# 220VAC_power_control.net
KiCad netlist of a schematic drawn in EAGLE
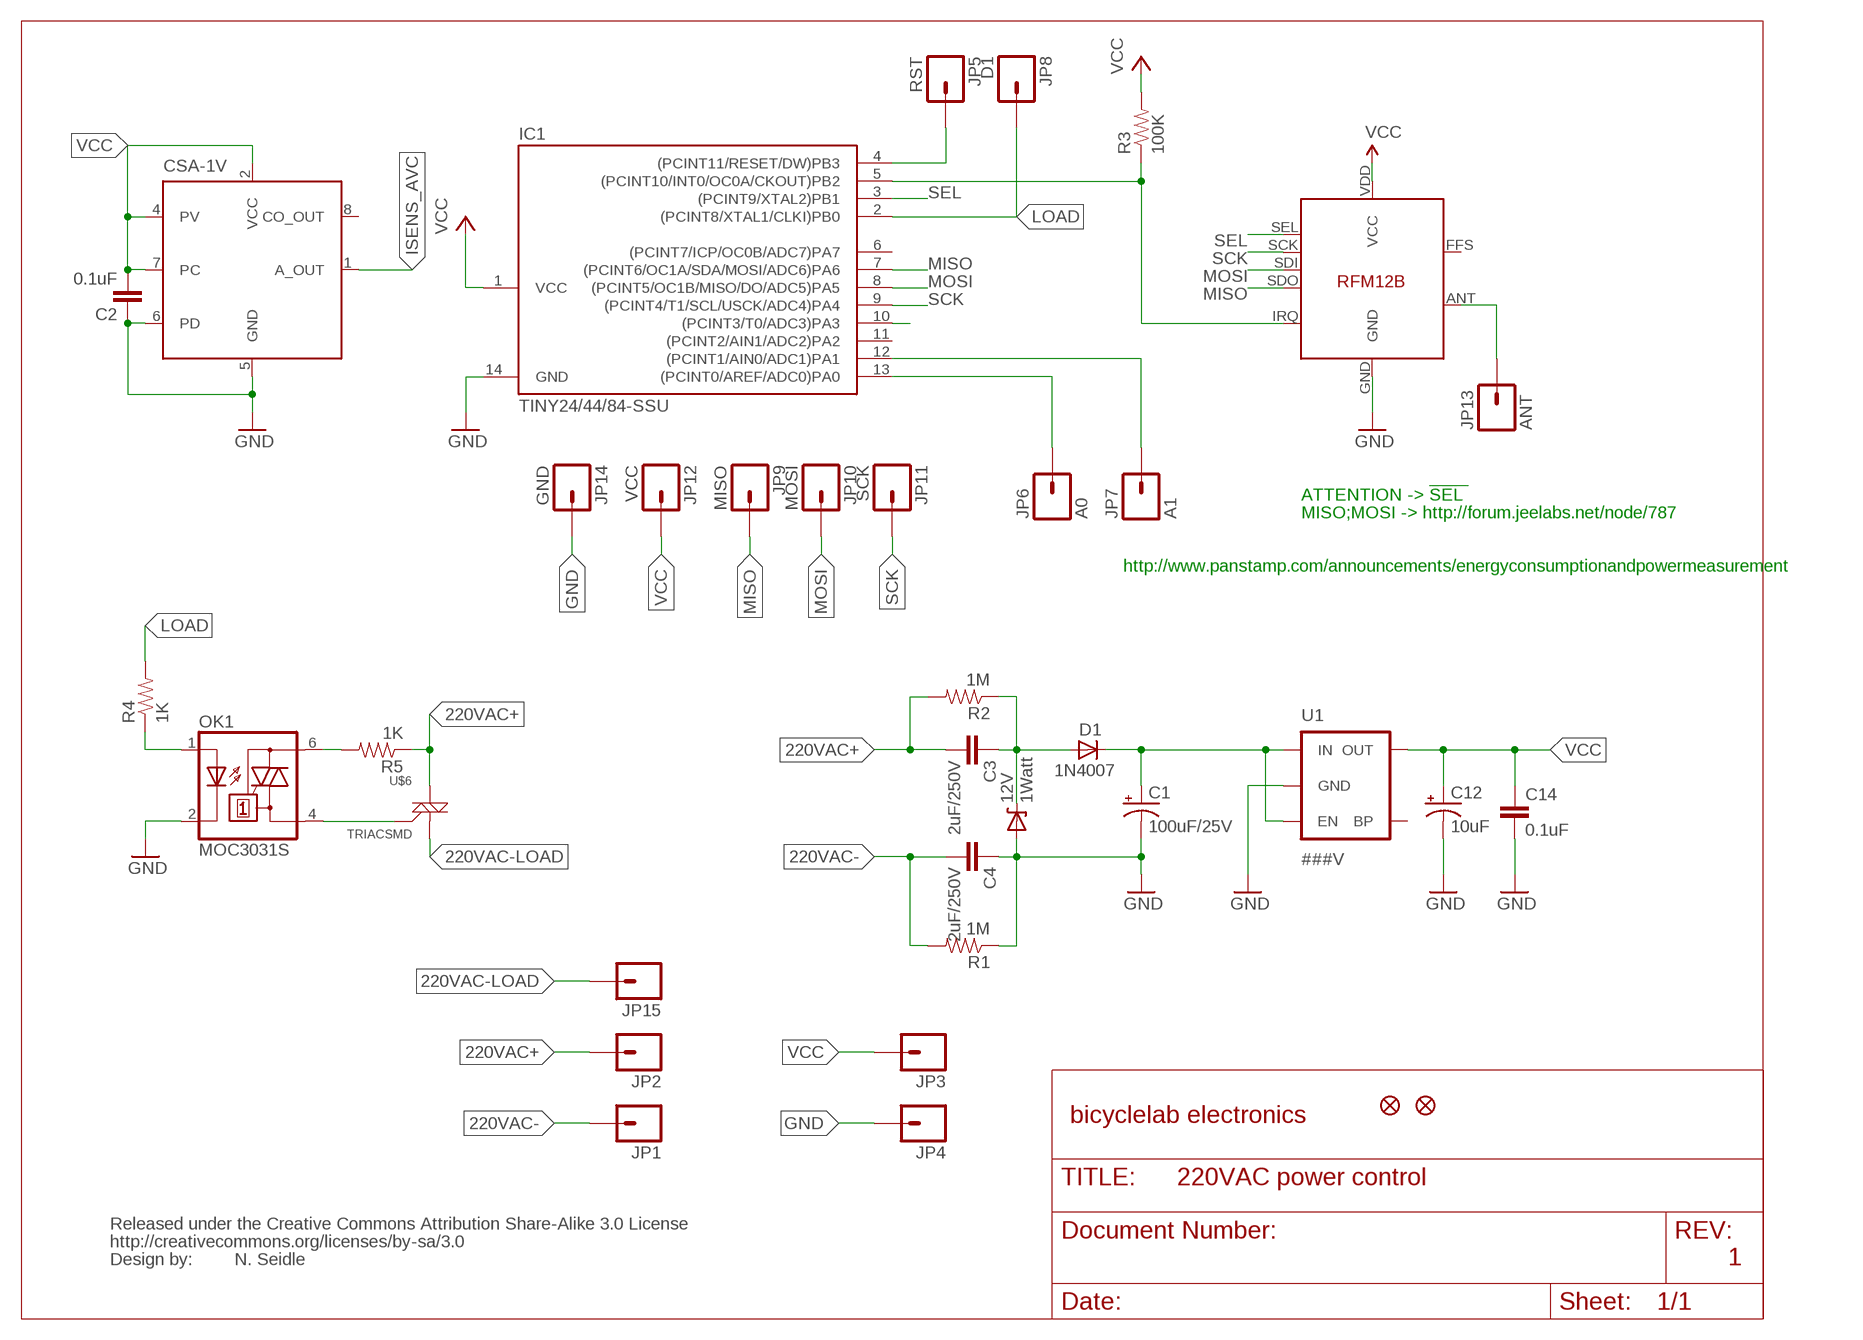
[diagram p0: schematic, sheet 1]

(export (version "E")
  (design (tool "Eeschema 10.0.6"))
  (components
    (comp (ref "12V")
      (value "1Watt")
      (footprint "eagle-import:SMB-DIODE")
      (libsource (lib "eagle-import") (part "DIODE-ZENERSMB"))
    )
    (comp (ref "C1")
      (value "100uF/25V")
      (footprint "eagle-import:EIA7343")
      (libsource (lib "eagle-import") (part "CAP_POL7343"))
    )
    (comp (ref "C2")
      (value "0.1uF")
      (footprint "eagle-import:0603-CAP")
      (libsource (lib "eagle-import") (part "CAP0603-CAP"))
    )
    (comp (ref "C3")
      (value "2uF/250V")
      (footprint "eagle-import:0402-CAP")
      (libsource (lib "eagle-import") (part "CAP0402-CAP"))
    )
    (comp (ref "C4")
      (value "2uF/250V")
      (footprint "eagle-import:0402-CAP")
      (libsource (lib "eagle-import") (part "CAP0402-CAP"))
    )
    (comp (ref "C12")
      (value "10uF")
      (footprint "eagle-import:EIA3216")
      (libsource (lib "eagle-import") (part "CAP_POL1206"))
    )
    (comp (ref "C14")
      (value "0.1uF")
      (footprint "eagle-import:0603-CAP")
      (libsource (lib "eagle-import") (part "CAP0603-CAP"))
    )
    (comp (ref "D1")
      (value "1N4007")
      (footprint "eagle-import:SMA-DIODE")
      (libsource (lib "eagle-import") (part "DIODESMA"))
    )
    (comp (ref "IC1")
      (value "TINY24/44/84-SSU")
      (footprint "eagle-import:SOIC14")
      (libsource (lib "eagle-import") (part "TINY24/44/84-SSU"))
    )
    (comp (ref "JP1")
      (value "M01PTH")
      (footprint "eagle-import:1X01")
      (libsource (lib "eagle-import") (part "M01PTH"))
    )
    (comp (ref "JP2")
      (value "M01PTH")
      (footprint "eagle-import:1X01")
      (libsource (lib "eagle-import") (part "M01PTH"))
    )
    (comp (ref "JP3")
      (value "M01PTH")
      (footprint "eagle-import:1X01")
      (libsource (lib "eagle-import") (part "M01PTH"))
    )
    (comp (ref "JP4")
      (value "M01PTH")
      (footprint "eagle-import:1X01")
      (libsource (lib "eagle-import") (part "M01PTH"))
    )
    (comp (ref "JP5")
      (value "RST")
      (footprint "eagle-import:1X01_POGOPIN_HOLE_0.58")
      (libsource (lib "eagle-import") (part "M01POGOPIN_HOLE_0.58"))
    )
    (comp (ref "JP6")
      (value "A0")
      (footprint "eagle-import:1X01_POGOPIN_HOLE_0.58")
      (libsource (lib "eagle-import") (part "M01POGOPIN_HOLE_0.58"))
    )
    (comp (ref "JP7")
      (value "A1")
      (footprint "eagle-import:1X01_POGOPIN_HOLE_0.58")
      (libsource (lib "eagle-import") (part "M01POGOPIN_HOLE_0.58"))
    )
    (comp (ref "JP8")
      (value "D1")
      (footprint "eagle-import:1X01_POGOPIN_HOLE_0.58")
      (libsource (lib "eagle-import") (part "M01POGOPIN_HOLE_0.58"))
    )
    (comp (ref "JP9")
      (value "MISO")
      (footprint "eagle-import:1X01_POGOPIN_HOLE_0.58")
      (libsource (lib "eagle-import") (part "M01POGOPIN_HOLE_0.58"))
    )
    (comp (ref "JP10")
      (value "MOSI")
      (footprint "eagle-import:1X01_POGOPIN_HOLE_0.58")
      (libsource (lib "eagle-import") (part "M01POGOPIN_HOLE_0.58"))
    )
    (comp (ref "JP11")
      (value "SCK")
      (footprint "eagle-import:1X01_POGOPIN_HOLE_0.58")
      (libsource (lib "eagle-import") (part "M01POGOPIN_HOLE_0.58"))
    )
    (comp (ref "JP12")
      (value "VCC")
      (footprint "eagle-import:1X01_POGOPIN_HOLE_0.58")
      (libsource (lib "eagle-import") (part "M01POGOPIN_HOLE_0.58"))
    )
    (comp (ref "JP13")
      (value "ANT")
      (footprint "eagle-import:PAD-1.5X4.5")
      (libsource (lib "eagle-import") (part "M01SMD-4.5X1.5"))
    )
    (comp (ref "JP14")
      (value "GND")
      (footprint "eagle-import:1X01NS")
      (libsource (lib "eagle-import") (part "M01SMDNS"))
    )
    (comp (ref "JP15")
      (value "M01PTH")
      (footprint "eagle-import:1X01")
      (libsource (lib "eagle-import") (part "M01PTH"))
    )
    (comp (ref "OK1")
      (value "MOC3031S")
      (footprint "eagle-import:DIL6-SMD")
      (fields (field (name "MF") "FAIRCHILD SEMICONDUCTOR") (field (name "MPN") "MOC3031SM"))
      (libsource (lib "eagle-import") (part "MOC30S31"))
    )
    (comp (ref "R1")
      (value "1M")
      (footprint "eagle-import:0402-RES")
      (libsource (lib "eagle-import") (part "RESISTOR0402-RES"))
    )
    (comp (ref "R2")
      (value "1M")
      (footprint "eagle-import:0402-RES")
      (libsource (lib "eagle-import") (part "RESISTOR0402-RES"))
    )
    (comp (ref "R3")
      (value "100K")
      (footprint "eagle-import:0805")
      (libsource (lib "eagle-import") (part "RESISTOR0805-RES"))
    )
    (comp (ref "R4")
      (value "1K")
      (footprint "eagle-import:0805")
      (libsource (lib "eagle-import") (part "RESISTOR0805-RES"))
    )
    (comp (ref "R5")
      (value "1K")
      (footprint "eagle-import:0805")
      (libsource (lib "eagle-import") (part "RESISTOR0805-RES"))
    )
    (comp (ref "U$1")
      (value "CSA-1V")
      (footprint "eagle-import:SOIC8")
      (libsource (lib "eagle-import") (part "CSA-1V"))
    )
    (comp (ref "U$2")
      (value "RFM12B")
      (footprint "eagle-import:RFM12B")
      (libsource (lib "eagle-import") (part "RFM12B"))
    )
    (comp (ref "U$3")
      (value "FIDUCIAL1X2")
      (footprint "eagle-import:FIDUCIAL-1X2")
      (libsource (lib "eagle-import") (part "FIDUCIAL1X2"))
    )
    (comp (ref "U$4")
      (value "FIDUCIAL1X2")
      (footprint "eagle-import:FIDUCIAL-1X2")
      (libsource (lib "eagle-import") (part "FIDUCIAL1X2"))
    )
    (comp (ref "U$5")
      (value "CREATIVE_COMMONS")
      (footprint "eagle-import:CREATIVE_COMMONS")
      (libsource (lib "eagle-import") (part "CREATIVE_COMMONS"))
    )
    (comp (ref "U$6")
      (value "TRIACSMD")
      (footprint "eagle-import:SOT223")
      (libsource (lib "eagle-import") (part "TRIACSMD"))
    )
    (comp (ref "U1")
      (value "###V")
      (footprint "eagle-import:SOT23-5")
      (libsource (lib "eagle-import") (part "V_REG_LDOSMD"))
    )
  )
  (nets
    (net (code "1") (name "/SEL") (class "Default")
      (node (ref "IC1") (pin "3") (pinfunction "(PCINT9/XTAL2)PB1_3") (pintype "bidirectional"))
      (node (ref "U$2") (pin "SEL") (pinfunction "SEL_SEL") (pintype "input"))
    )
    (net (code "2") (name "220VAC+") (class "Default")
      (node (ref "C3") (pin "2") (pinfunction "2_2") (pintype "passive"))
      (node (ref "JP2") (pin "1") (pinfunction "1_1") (pintype "passive"))
      (node (ref "R2") (pin "2") (pinfunction "2_2") (pintype "passive"))
      (node (ref "R5") (pin "1") (pinfunction "1_1") (pintype "passive"))
      (node (ref "U$6") (pin "2") (pinfunction "M2_2") (pintype "bidirectional"))
    )
    (net (code "3") (name "220VAC-") (class "Default")
      (node (ref "C4") (pin "2") (pinfunction "2_2") (pintype "passive"))
      (node (ref "JP1") (pin "1") (pinfunction "1_1") (pintype "passive"))
      (node (ref "R1") (pin "2") (pinfunction "2_2") (pintype "passive"))
    )
    (net (code "4") (name "220VAC-LOAD") (class "Default")
      (node (ref "JP15") (pin "1") (pinfunction "1_1") (pintype "passive"))
      (node (ref "U$6") (pin "1") (pinfunction "M1_1") (pintype "bidirectional"))
    )
    (net (code "5") (name "GND") (class "Default")
      (node (ref "12V") (pin "A") (pinfunction "A_A") (pintype "passive"))
      (node (ref "C1") (pin "C") (pinfunction "-_C") (pintype "passive"))
      (node (ref "C12") (pin "C") (pinfunction "-_C") (pintype "passive"))
      (node (ref "C14") (pin "2") (pinfunction "2_2") (pintype "passive"))
      (node (ref "C2") (pin "1") (pinfunction "1_1") (pintype "passive"))
      (node (ref "C4") (pin "1") (pinfunction "1_1") (pintype "passive"))
      (node (ref "IC1") (pin "14") (pinfunction "GND_14") (pintype "power_in"))
      (node (ref "JP14") (pin "1") (pinfunction "1_1") (pintype "passive"))
      (node (ref "JP4") (pin "1") (pinfunction "1_1") (pintype "passive"))
      (node (ref "OK1") (pin "2") (pinfunction "C_2") (pintype "passive"))
      (node (ref "R1") (pin "1") (pinfunction "1_1") (pintype "passive"))
      (node (ref "U$1") (pin "5") (pinfunction "GND_5") (pintype "power_in"))
      (node (ref "U$1") (pin "6") (pinfunction "PD_6") (pintype "input"))
      (node (ref "U$2") (pin "GND") (pinfunction "GND_GND") (pintype "power_in"))
      (node (ref "U1") (pin "2") (pinfunction "GND_2") (pintype "input"))
    )
    (net (code "6") (name "ISENS_AVC") (class "Default")
      (node (ref "IC1") (pin "12") (pinfunction "(PCINT1/AIN0/ADC1)PA1_12") (pintype "bidirectional"))
      (node (ref "JP7") (pin "1") (pinfunction "1_1") (pintype "passive"))
      (node (ref "U$1") (pin "1") (pinfunction "A_OUT_1") (pintype "output"))
    )
    (net (code "7") (name "LOAD") (class "Default")
      (node (ref "IC1") (pin "2") (pinfunction "(PCINT8/XTAL1/CLKI)PB0_2") (pintype "bidirectional"))
      (node (ref "JP8") (pin "1") (pinfunction "1_1") (pintype "passive"))
      (node (ref "R4") (pin "2") (pinfunction "2_2") (pintype "passive"))
    )
    (net (code "8") (name "MISO") (class "Default")
      (node (ref "IC1") (pin "7") (pinfunction "(PCINT6/OC1A/SDA/MOSI/ADC6)PA6_7") (pintype "bidirectional"))
      (node (ref "JP9") (pin "1") (pinfunction "1_1") (pintype "passive"))
      (node (ref "U$2") (pin "SDO") (pinfunction "SDO_SDO") (pintype "output"))
    )
    (net (code "9") (name "MOSI") (class "Default")
      (node (ref "IC1") (pin "8") (pinfunction "(PCINT5/OC1B/MISO/DO/ADC5)PA5_8") (pintype "bidirectional"))
      (node (ref "JP10") (pin "1") (pinfunction "1_1") (pintype "passive"))
      (node (ref "U$2") (pin "SDI") (pinfunction "SDI_SDI") (pintype "input"))
    )
    (net (code "10") (name "Net-(12V-PadC)") (class "Default")
      (node (ref "12V") (pin "C") (pinfunction "C_C") (pintype "passive"))
      (node (ref "C3") (pin "1") (pinfunction "1_1") (pintype "passive"))
      (node (ref "D1") (pin "A") (pinfunction "A_A") (pintype "passive"))
      (node (ref "R2") (pin "1") (pinfunction "1_1") (pintype "passive"))
    )
    (net (code "11") (name "Net-(C1-+)") (class "Default")
      (node (ref "C1") (pin "A") (pinfunction "+_A") (pintype "passive"))
      (node (ref "D1") (pin "C") (pinfunction "C_C") (pintype "passive"))
      (node (ref "U1") (pin "1") (pinfunction "IN_1") (pintype "input"))
      (node (ref "U1") (pin "3") (pinfunction "EN_3") (pintype "input"))
    )
    (net (code "12") (name "Net-(IC1-(PCINT0{slash}AREF{slash}ADC0)PA0)") (class "Default")
      (node (ref "IC1") (pin "13") (pinfunction "(PCINT0/AREF/ADC0)PA0_13") (pintype "bidirectional"))
      (node (ref "JP6") (pin "1") (pinfunction "1_1") (pintype "passive"))
    )
    (net (code "13") (name "Net-(IC1-(PCINT10{slash}INT0{slash}OC0A{slash}CKOUT)PB2)") (class "Default")
      (node (ref "IC1") (pin "5") (pinfunction "(PCINT10/INT0/OC0A/CKOUT)PB2_5") (pintype "bidirectional"))
      (node (ref "R3") (pin "1") (pinfunction "1_1") (pintype "passive"))
      (node (ref "U$2") (pin "IRQ") (pinfunction "IRQ_IRQ") (pintype "open_collector"))
    )
    (net (code "14") (name "Net-(IC1-(PCINT11{slash}RESET{slash}DW)PB3)") (class "Default")
      (node (ref "IC1") (pin "4") (pinfunction "(PCINT11/RESET/DW)PB3_4") (pintype "bidirectional"))
      (node (ref "JP5") (pin "1") (pinfunction "1_1") (pintype "passive"))
    )
    (net (code "15") (name "Net-(JP13-1)") (class "Default")
      (node (ref "JP13") (pin "P$1") (pinfunction "1_P$1") (pintype "passive"))
      (node (ref "U$2") (pin "ANT") (pinfunction "ANT_ANT") (pintype "passive"))
    )
    (net (code "16") (name "Net-(OK1-A)") (class "Default")
      (node (ref "OK1") (pin "1") (pinfunction "A_1") (pintype "passive"))
      (node (ref "R4") (pin "1") (pinfunction "1_1") (pintype "passive"))
    )
    (net (code "17") (name "Net-(OK1-A1)") (class "Default")
      (node (ref "OK1") (pin "4") (pinfunction "A1_4") (pintype "passive"))
      (node (ref "U$6") (pin "3") (pinfunction "G_3") (pintype "bidirectional"))
    )
    (net (code "18") (name "Net-(OK1-A2)") (class "Default")
      (node (ref "OK1") (pin "6") (pinfunction "A2_6") (pintype "passive"))
      (node (ref "R5") (pin "2") (pinfunction "2_2") (pintype "passive"))
    )
    (net (code "19") (name "SCK") (class "Default")
      (node (ref "IC1") (pin "9") (pinfunction "(PCINT4/T1/SCL/USCK/ADC4)PA4_9") (pintype "bidirectional"))
      (node (ref "JP11") (pin "1") (pinfunction "1_1") (pintype "passive"))
      (node (ref "U$2") (pin "SCK") (pinfunction "SCK_SCK") (pintype "input"))
    )
    (net (code "20") (name "VCC") (class "Default")
      (node (ref "C12") (pin "A") (pinfunction "+_A") (pintype "passive"))
      (node (ref "C14") (pin "1") (pinfunction "1_1") (pintype "passive"))
      (node (ref "C2") (pin "2") (pinfunction "2_2") (pintype "passive"))
      (node (ref "IC1") (pin "1") (pinfunction "VCC_1") (pintype "power_in"))
      (node (ref "JP12") (pin "1") (pinfunction "1_1") (pintype "passive"))
      (node (ref "JP3") (pin "1") (pinfunction "1_1") (pintype "passive"))
      (node (ref "R3") (pin "2") (pinfunction "2_2") (pintype "passive"))
      (node (ref "U$1") (pin "2") (pinfunction "VCC_2") (pintype "power_in"))
      (node (ref "U$1") (pin "4") (pinfunction "PV_4") (pintype "input"))
      (node (ref "U$1") (pin "7") (pinfunction "PC_7") (pintype "input"))
      (node (ref "U$2") (pin "VDD") (pinfunction "VCC_VDD") (pintype "power_in"))
      (node (ref "U1") (pin "5") (pinfunction "OUT_5") (pintype "passive"))
    )
    (net (code "21") (name "unconnected-(IC1-(PCINT2{slash}AIN1{slash}ADC2)PA2-Pad11)") (class "Default")
      (node (ref "IC1") (pin "11") (pinfunction "(PCINT2/AIN1/ADC2)PA2_11") (pintype "bidirectional"))
    )
    (net (code "22") (name "unconnected-(IC1-(PCINT3{slash}T0{slash}ADC3)PA3-Pad10)") (class "Default")
      (node (ref "IC1") (pin "10") (pinfunction "(PCINT3/T0/ADC3)PA3_10") (pintype "bidirectional"))
    )
    (net (code "23") (name "unconnected-(IC1-(PCINT7{slash}ICP{slash}OC0B{slash}ADC7)PA7-Pad6)") (class "Default")
      (node (ref "IC1") (pin "6") (pinfunction "(PCINT7/ICP/OC0B/ADC7)PA7_6") (pintype "bidirectional"))
    )
    (net (code "24") (name "unconnected-(U$1-CO_OUT-Pad8)") (class "Default")
      (node (ref "U$1") (pin "8") (pinfunction "CO_OUT_8") (pintype "output"))
    )
    (net (code "25") (name "unconnected-(U$1-NC-Pad3)") (class "Default")
      (node (ref "U$1") (pin "3") (pinfunction "NC_3") (pintype "no_connect"))
    )
    (net (code "26") (name "unconnected-(U$2-PadFFS)") (class "Default")
      (node (ref "U$2") (pin "FFS") (pinfunction "FFS_FFS") (pintype "bidirectional"))
    )
    (net (code "27") (name "unconnected-(U1-BP-Pad4)") (class "Default")
      (node (ref "U1") (pin "4") (pinfunction "BP_4") (pintype "input"))
    )
  )
)
